# 280113_Battery_Connector_UEBK-30256_1_0.net
KiCad netlist of a schematic drawn in EAGLE
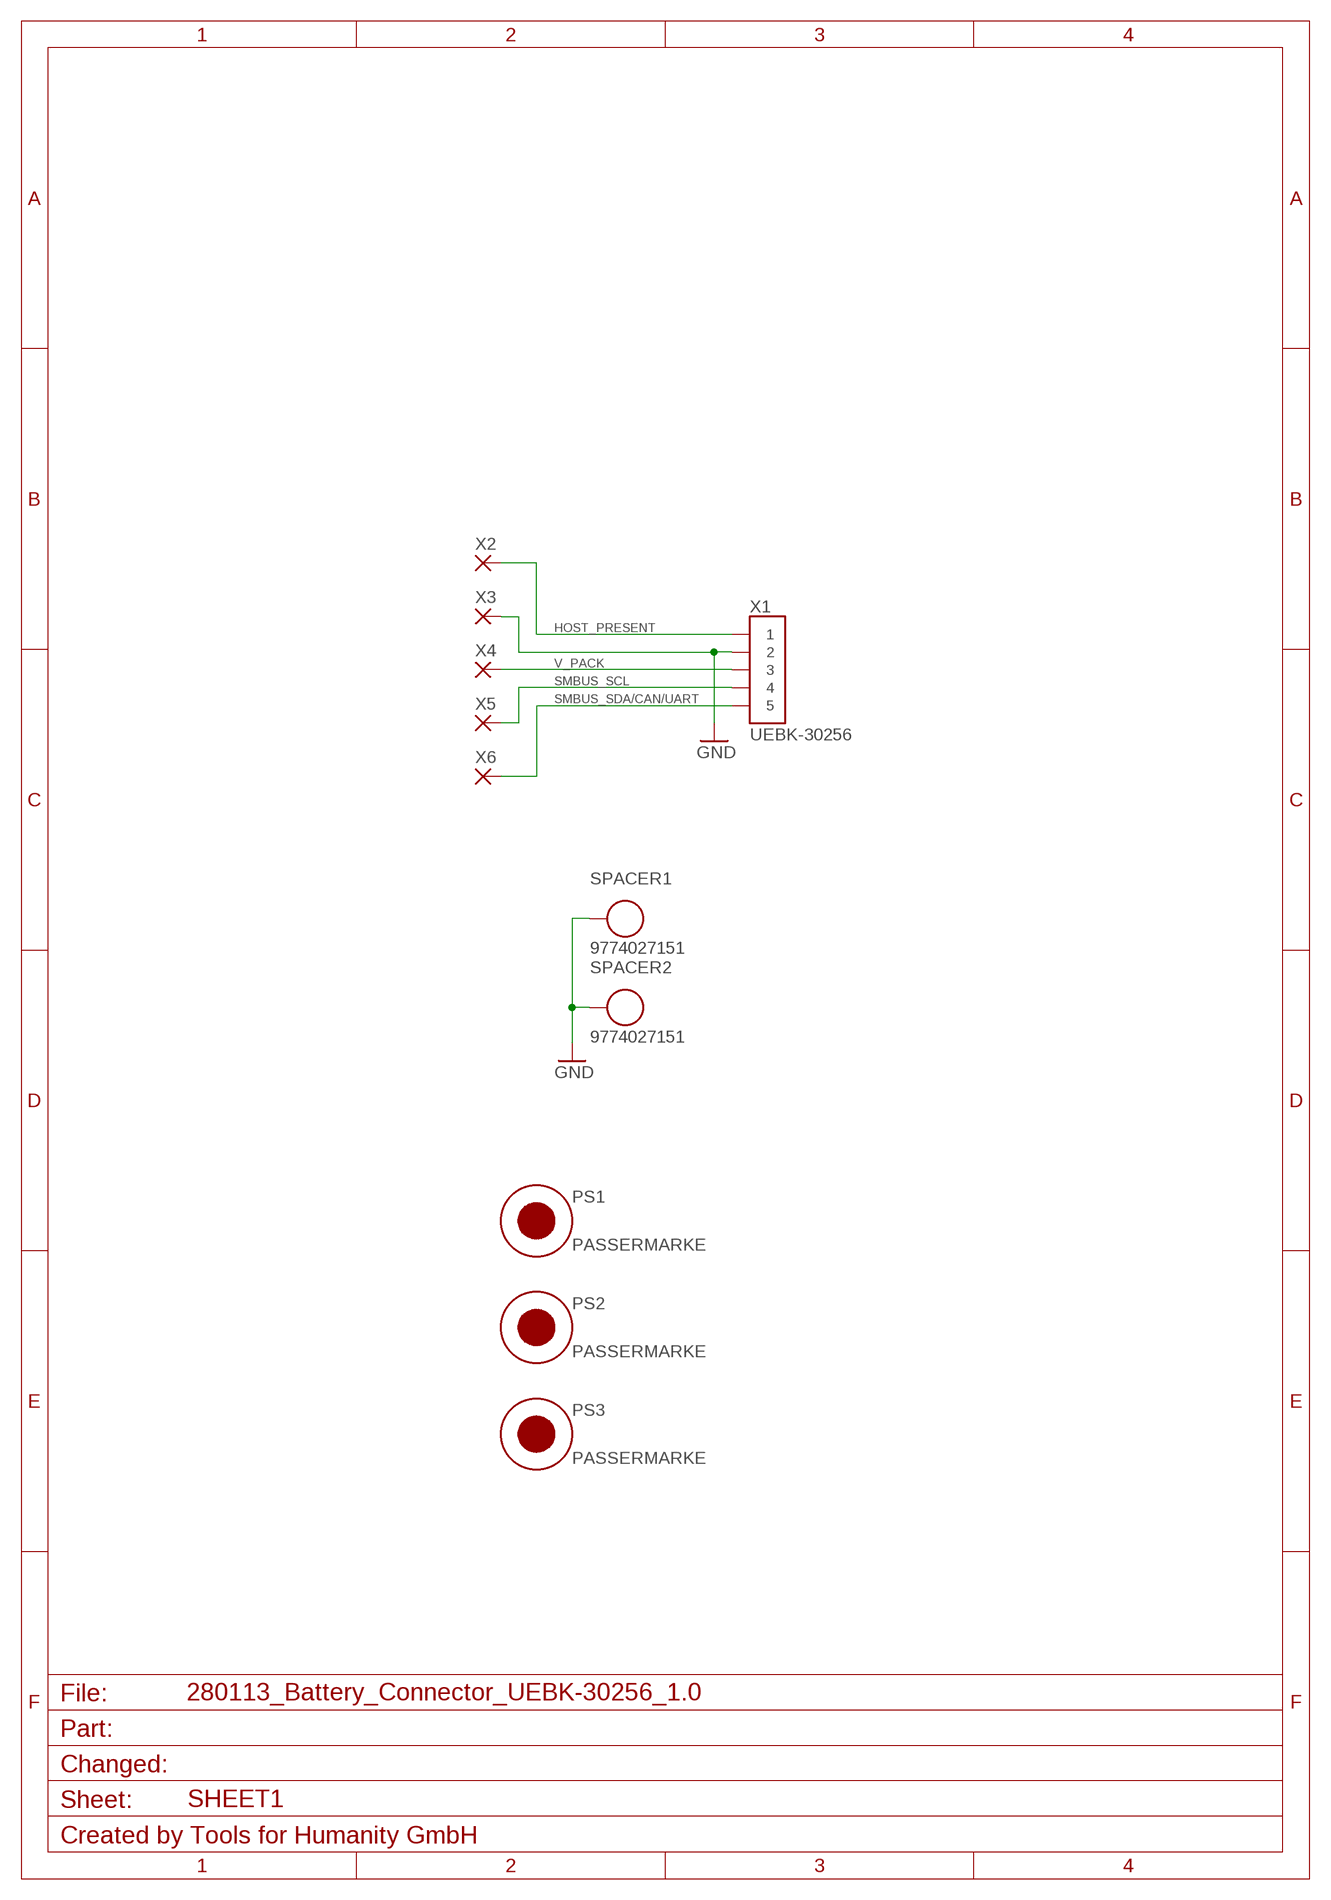
[diagram p0: schematic, sheet 1]

(export (version "E")
  (design (tool "Eeschema 10.0.6"))
  (components
    (comp (ref "PS1")
      (value "PASSERMARKE")
      (footprint "eagle-import:PASSERMARKE")
      (libsource (lib "eagle-import") (part "PASSERMARKE"))
    )
    (comp (ref "PS2")
      (value "PASSERMARKE")
      (footprint "eagle-import:PASSERMARKE")
      (libsource (lib "eagle-import") (part "PASSERMARKE"))
    )
    (comp (ref "PS3")
      (value "PASSERMARKE")
      (footprint "eagle-import:PASSERMARKE")
      (libsource (lib "eagle-import") (part "PASSERMARKE"))
    )
    (comp (ref "SPACER1")
      (value "9774027151")
      (footprint "eagle-import:WA-SMSI_9774027151_WUERTH")
      (fields (field (name "MANUFACTURER") "Wuerth"))
      (libsource (lib "eagle-import") (part "9774027151"))
    )
    (comp (ref "SPACER2")
      (value "9774027151")
      (footprint "eagle-import:WA-SMSI_9774027151_WUERTH")
      (fields (field (name "MANUFACTURER") "Wuerth"))
      (libsource (lib "eagle-import") (part "9774027151"))
    )
    (comp (ref "X1")
      (value "UEBK-30256")
      (footprint "eagle-import:UEBK-30256_UWE")
      (fields (field (name "MANUFACTURER") "uwe electronic GmbH"))
      (libsource (lib "eagle-import") (part "UEBK-30256"))
    )
    (comp (ref "X2")
      (value "PAD_RECT_VIAS_3.3X10.0MM_TOP_BOT")
      (footprint "eagle-import:PAD_RECT_VIAS_3.3X10.0MM_TOP_BOT")
      (libsource (lib "eagle-import") (part "PAD_RECT_VIAS_3.3X10.0MM_TOP_BOT"))
    )
    (comp (ref "X3")
      (value "PAD_RECT_VIAS_3.3X10.0MM_TOP_BOT")
      (footprint "eagle-import:PAD_RECT_VIAS_3.3X10.0MM_TOP_BOT")
      (libsource (lib "eagle-import") (part "PAD_RECT_VIAS_3.3X10.0MM_TOP_BOT"))
    )
    (comp (ref "X4")
      (value "PAD_RECT_VIAS_3.3X10.0MM_TOP_BOT")
      (footprint "eagle-import:PAD_RECT_VIAS_3.3X10.0MM_TOP_BOT")
      (libsource (lib "eagle-import") (part "PAD_RECT_VIAS_3.3X10.0MM_TOP_BOT"))
    )
    (comp (ref "X5")
      (value "PAD_RECT_VIAS_3.3X10.0MM_TOP_BOT")
      (footprint "eagle-import:PAD_RECT_VIAS_3.3X10.0MM_TOP_BOT")
      (libsource (lib "eagle-import") (part "PAD_RECT_VIAS_3.3X10.0MM_TOP_BOT"))
    )
    (comp (ref "X6")
      (value "PAD_RECT_VIAS_3.3X10.0MM_TOP_BOT")
      (footprint "eagle-import:PAD_RECT_VIAS_3.3X10.0MM_TOP_BOT")
      (libsource (lib "eagle-import") (part "PAD_RECT_VIAS_3.3X10.0MM_TOP_BOT"))
    )
  )
  (nets
    (net (code "1") (name "/HOST_PRESENT") (class "Default")
      (node (ref "X1") (pin "1") (pinfunction "1_1") (pintype "passive"))
      (node (ref "X2") (pin "1") (pinfunction "P_1") (pintype "passive"))
      (node (ref "X2") (pin "2") (pinfunction "P_2") (pintype "passive"))
      (node (ref "X2") (pin "P$1") (pinfunction "P_P$1") (pintype "passive"))
      (node (ref "X2") (pin "P$10") (pinfunction "P_P$10") (pintype "passive"))
      (node (ref "X2") (pin "P$11") (pinfunction "P_P$11") (pintype "passive"))
      (node (ref "X2") (pin "P$12") (pinfunction "P_P$12") (pintype "passive"))
      (node (ref "X2") (pin "P$13") (pinfunction "P_P$13") (pintype "passive"))
      (node (ref "X2") (pin "P$14") (pinfunction "P_P$14") (pintype "passive"))
      (node (ref "X2") (pin "P$15") (pinfunction "P_P$15") (pintype "passive"))
      (node (ref "X2") (pin "P$16") (pinfunction "P_P$16") (pintype "passive"))
      (node (ref "X2") (pin "P$17") (pinfunction "P_P$17") (pintype "passive"))
      (node (ref "X2") (pin "P$18") (pinfunction "P_P$18") (pintype "passive"))
      (node (ref "X2") (pin "P$19") (pinfunction "P_P$19") (pintype "passive"))
      (node (ref "X2") (pin "P$2") (pinfunction "P_P$2") (pintype "passive"))
      (node (ref "X2") (pin "P$20") (pinfunction "P_P$20") (pintype "passive"))
      (node (ref "X2") (pin "P$21") (pinfunction "P_P$21") (pintype "passive"))
      (node (ref "X2") (pin "P$22") (pinfunction "P_P$22") (pintype "passive"))
      (node (ref "X2") (pin "P$23") (pinfunction "P_P$23") (pintype "passive"))
      (node (ref "X2") (pin "P$24") (pinfunction "P_P$24") (pintype "passive"))
      (node (ref "X2") (pin "P$25") (pinfunction "P_P$25") (pintype "passive"))
      (node (ref "X2") (pin "P$26") (pinfunction "P_P$26") (pintype "passive"))
      (node (ref "X2") (pin "P$27") (pinfunction "P_P$27") (pintype "passive"))
      (node (ref "X2") (pin "P$3") (pinfunction "P_P$3") (pintype "passive"))
      (node (ref "X2") (pin "P$4") (pinfunction "P_P$4") (pintype "passive"))
      (node (ref "X2") (pin "P$5") (pinfunction "P_P$5") (pintype "passive"))
      (node (ref "X2") (pin "P$6") (pinfunction "P_P$6") (pintype "passive"))
      (node (ref "X2") (pin "P$7") (pinfunction "P_P$7") (pintype "passive"))
      (node (ref "X2") (pin "P$8") (pinfunction "P_P$8") (pintype "passive"))
      (node (ref "X2") (pin "P$9") (pinfunction "P_P$9") (pintype "passive"))
    )
    (net (code "2") (name "/SMBUS_SCL") (class "Default")
      (node (ref "X1") (pin "4") (pinfunction "4_4") (pintype "passive"))
      (node (ref "X5") (pin "1") (pinfunction "P_1") (pintype "passive"))
      (node (ref "X5") (pin "2") (pinfunction "P_2") (pintype "passive"))
      (node (ref "X5") (pin "P$1") (pinfunction "P_P$1") (pintype "passive"))
      (node (ref "X5") (pin "P$10") (pinfunction "P_P$10") (pintype "passive"))
      (node (ref "X5") (pin "P$11") (pinfunction "P_P$11") (pintype "passive"))
      (node (ref "X5") (pin "P$12") (pinfunction "P_P$12") (pintype "passive"))
      (node (ref "X5") (pin "P$13") (pinfunction "P_P$13") (pintype "passive"))
      (node (ref "X5") (pin "P$14") (pinfunction "P_P$14") (pintype "passive"))
      (node (ref "X5") (pin "P$15") (pinfunction "P_P$15") (pintype "passive"))
      (node (ref "X5") (pin "P$16") (pinfunction "P_P$16") (pintype "passive"))
      (node (ref "X5") (pin "P$17") (pinfunction "P_P$17") (pintype "passive"))
      (node (ref "X5") (pin "P$18") (pinfunction "P_P$18") (pintype "passive"))
      (node (ref "X5") (pin "P$19") (pinfunction "P_P$19") (pintype "passive"))
      (node (ref "X5") (pin "P$2") (pinfunction "P_P$2") (pintype "passive"))
      (node (ref "X5") (pin "P$20") (pinfunction "P_P$20") (pintype "passive"))
      (node (ref "X5") (pin "P$21") (pinfunction "P_P$21") (pintype "passive"))
      (node (ref "X5") (pin "P$22") (pinfunction "P_P$22") (pintype "passive"))
      (node (ref "X5") (pin "P$23") (pinfunction "P_P$23") (pintype "passive"))
      (node (ref "X5") (pin "P$24") (pinfunction "P_P$24") (pintype "passive"))
      (node (ref "X5") (pin "P$25") (pinfunction "P_P$25") (pintype "passive"))
      (node (ref "X5") (pin "P$26") (pinfunction "P_P$26") (pintype "passive"))
      (node (ref "X5") (pin "P$27") (pinfunction "P_P$27") (pintype "passive"))
      (node (ref "X5") (pin "P$3") (pinfunction "P_P$3") (pintype "passive"))
      (node (ref "X5") (pin "P$4") (pinfunction "P_P$4") (pintype "passive"))
      (node (ref "X5") (pin "P$5") (pinfunction "P_P$5") (pintype "passive"))
      (node (ref "X5") (pin "P$6") (pinfunction "P_P$6") (pintype "passive"))
      (node (ref "X5") (pin "P$7") (pinfunction "P_P$7") (pintype "passive"))
      (node (ref "X5") (pin "P$8") (pinfunction "P_P$8") (pintype "passive"))
      (node (ref "X5") (pin "P$9") (pinfunction "P_P$9") (pintype "passive"))
    )
    (net (code "3") (name "/SMBUS_SDA{slash}CAN{slash}UART") (class "Default")
      (node (ref "X1") (pin "5") (pinfunction "5_5") (pintype "passive"))
      (node (ref "X6") (pin "1") (pinfunction "P_1") (pintype "passive"))
      (node (ref "X6") (pin "2") (pinfunction "P_2") (pintype "passive"))
      (node (ref "X6") (pin "P$1") (pinfunction "P_P$1") (pintype "passive"))
      (node (ref "X6") (pin "P$10") (pinfunction "P_P$10") (pintype "passive"))
      (node (ref "X6") (pin "P$11") (pinfunction "P_P$11") (pintype "passive"))
      (node (ref "X6") (pin "P$12") (pinfunction "P_P$12") (pintype "passive"))
      (node (ref "X6") (pin "P$13") (pinfunction "P_P$13") (pintype "passive"))
      (node (ref "X6") (pin "P$14") (pinfunction "P_P$14") (pintype "passive"))
      (node (ref "X6") (pin "P$15") (pinfunction "P_P$15") (pintype "passive"))
      (node (ref "X6") (pin "P$16") (pinfunction "P_P$16") (pintype "passive"))
      (node (ref "X6") (pin "P$17") (pinfunction "P_P$17") (pintype "passive"))
      (node (ref "X6") (pin "P$18") (pinfunction "P_P$18") (pintype "passive"))
      (node (ref "X6") (pin "P$19") (pinfunction "P_P$19") (pintype "passive"))
      (node (ref "X6") (pin "P$2") (pinfunction "P_P$2") (pintype "passive"))
      (node (ref "X6") (pin "P$20") (pinfunction "P_P$20") (pintype "passive"))
      (node (ref "X6") (pin "P$21") (pinfunction "P_P$21") (pintype "passive"))
      (node (ref "X6") (pin "P$22") (pinfunction "P_P$22") (pintype "passive"))
      (node (ref "X6") (pin "P$23") (pinfunction "P_P$23") (pintype "passive"))
      (node (ref "X6") (pin "P$24") (pinfunction "P_P$24") (pintype "passive"))
      (node (ref "X6") (pin "P$25") (pinfunction "P_P$25") (pintype "passive"))
      (node (ref "X6") (pin "P$26") (pinfunction "P_P$26") (pintype "passive"))
      (node (ref "X6") (pin "P$27") (pinfunction "P_P$27") (pintype "passive"))
      (node (ref "X6") (pin "P$3") (pinfunction "P_P$3") (pintype "passive"))
      (node (ref "X6") (pin "P$4") (pinfunction "P_P$4") (pintype "passive"))
      (node (ref "X6") (pin "P$5") (pinfunction "P_P$5") (pintype "passive"))
      (node (ref "X6") (pin "P$6") (pinfunction "P_P$6") (pintype "passive"))
      (node (ref "X6") (pin "P$7") (pinfunction "P_P$7") (pintype "passive"))
      (node (ref "X6") (pin "P$8") (pinfunction "P_P$8") (pintype "passive"))
      (node (ref "X6") (pin "P$9") (pinfunction "P_P$9") (pintype "passive"))
    )
    (net (code "4") (name "/V_PACK") (class "Default")
      (node (ref "X1") (pin "3") (pinfunction "3_3") (pintype "passive"))
      (node (ref "X4") (pin "1") (pinfunction "P_1") (pintype "passive"))
      (node (ref "X4") (pin "2") (pinfunction "P_2") (pintype "passive"))
      (node (ref "X4") (pin "P$1") (pinfunction "P_P$1") (pintype "passive"))
      (node (ref "X4") (pin "P$10") (pinfunction "P_P$10") (pintype "passive"))
      (node (ref "X4") (pin "P$11") (pinfunction "P_P$11") (pintype "passive"))
      (node (ref "X4") (pin "P$12") (pinfunction "P_P$12") (pintype "passive"))
      (node (ref "X4") (pin "P$13") (pinfunction "P_P$13") (pintype "passive"))
      (node (ref "X4") (pin "P$14") (pinfunction "P_P$14") (pintype "passive"))
      (node (ref "X4") (pin "P$15") (pinfunction "P_P$15") (pintype "passive"))
      (node (ref "X4") (pin "P$16") (pinfunction "P_P$16") (pintype "passive"))
      (node (ref "X4") (pin "P$17") (pinfunction "P_P$17") (pintype "passive"))
      (node (ref "X4") (pin "P$18") (pinfunction "P_P$18") (pintype "passive"))
      (node (ref "X4") (pin "P$19") (pinfunction "P_P$19") (pintype "passive"))
      (node (ref "X4") (pin "P$2") (pinfunction "P_P$2") (pintype "passive"))
      (node (ref "X4") (pin "P$20") (pinfunction "P_P$20") (pintype "passive"))
      (node (ref "X4") (pin "P$21") (pinfunction "P_P$21") (pintype "passive"))
      (node (ref "X4") (pin "P$22") (pinfunction "P_P$22") (pintype "passive"))
      (node (ref "X4") (pin "P$23") (pinfunction "P_P$23") (pintype "passive"))
      (node (ref "X4") (pin "P$24") (pinfunction "P_P$24") (pintype "passive"))
      (node (ref "X4") (pin "P$25") (pinfunction "P_P$25") (pintype "passive"))
      (node (ref "X4") (pin "P$26") (pinfunction "P_P$26") (pintype "passive"))
      (node (ref "X4") (pin "P$27") (pinfunction "P_P$27") (pintype "passive"))
      (node (ref "X4") (pin "P$3") (pinfunction "P_P$3") (pintype "passive"))
      (node (ref "X4") (pin "P$4") (pinfunction "P_P$4") (pintype "passive"))
      (node (ref "X4") (pin "P$5") (pinfunction "P_P$5") (pintype "passive"))
      (node (ref "X4") (pin "P$6") (pinfunction "P_P$6") (pintype "passive"))
      (node (ref "X4") (pin "P$7") (pinfunction "P_P$7") (pintype "passive"))
      (node (ref "X4") (pin "P$8") (pinfunction "P_P$8") (pintype "passive"))
      (node (ref "X4") (pin "P$9") (pinfunction "P_P$9") (pintype "passive"))
    )
    (net (code "5") (name "GND") (class "Default")
      (node (ref "SPACER1") (pin "2") (pinfunction "1_2") (pintype "passive"))
      (node (ref "SPACER1") (pin "3") (pinfunction "1_3") (pintype "passive"))
      (node (ref "SPACER2") (pin "2") (pinfunction "1_2") (pintype "passive"))
      (node (ref "SPACER2") (pin "3") (pinfunction "1_3") (pintype "passive"))
      (node (ref "X1") (pin "2") (pinfunction "2_2") (pintype "passive"))
      (node (ref "X3") (pin "1") (pinfunction "P_1") (pintype "passive"))
      (node (ref "X3") (pin "2") (pinfunction "P_2") (pintype "passive"))
      (node (ref "X3") (pin "P$1") (pinfunction "P_P$1") (pintype "passive"))
      (node (ref "X3") (pin "P$10") (pinfunction "P_P$10") (pintype "passive"))
      (node (ref "X3") (pin "P$11") (pinfunction "P_P$11") (pintype "passive"))
      (node (ref "X3") (pin "P$12") (pinfunction "P_P$12") (pintype "passive"))
      (node (ref "X3") (pin "P$13") (pinfunction "P_P$13") (pintype "passive"))
      (node (ref "X3") (pin "P$14") (pinfunction "P_P$14") (pintype "passive"))
      (node (ref "X3") (pin "P$15") (pinfunction "P_P$15") (pintype "passive"))
      (node (ref "X3") (pin "P$16") (pinfunction "P_P$16") (pintype "passive"))
      (node (ref "X3") (pin "P$17") (pinfunction "P_P$17") (pintype "passive"))
      (node (ref "X3") (pin "P$18") (pinfunction "P_P$18") (pintype "passive"))
      (node (ref "X3") (pin "P$19") (pinfunction "P_P$19") (pintype "passive"))
      (node (ref "X3") (pin "P$2") (pinfunction "P_P$2") (pintype "passive"))
      (node (ref "X3") (pin "P$20") (pinfunction "P_P$20") (pintype "passive"))
      (node (ref "X3") (pin "P$21") (pinfunction "P_P$21") (pintype "passive"))
      (node (ref "X3") (pin "P$22") (pinfunction "P_P$22") (pintype "passive"))
      (node (ref "X3") (pin "P$23") (pinfunction "P_P$23") (pintype "passive"))
      (node (ref "X3") (pin "P$24") (pinfunction "P_P$24") (pintype "passive"))
      (node (ref "X3") (pin "P$25") (pinfunction "P_P$25") (pintype "passive"))
      (node (ref "X3") (pin "P$26") (pinfunction "P_P$26") (pintype "passive"))
      (node (ref "X3") (pin "P$27") (pinfunction "P_P$27") (pintype "passive"))
      (node (ref "X3") (pin "P$3") (pinfunction "P_P$3") (pintype "passive"))
      (node (ref "X3") (pin "P$4") (pinfunction "P_P$4") (pintype "passive"))
      (node (ref "X3") (pin "P$5") (pinfunction "P_P$5") (pintype "passive"))
      (node (ref "X3") (pin "P$6") (pinfunction "P_P$6") (pintype "passive"))
      (node (ref "X3") (pin "P$7") (pinfunction "P_P$7") (pintype "passive"))
      (node (ref "X3") (pin "P$8") (pinfunction "P_P$8") (pintype "passive"))
      (node (ref "X3") (pin "P$9") (pinfunction "P_P$9") (pintype "passive"))
    )
  )
)
